# ps2.net
KiCad netlist of a schematic drawn in EAGLE
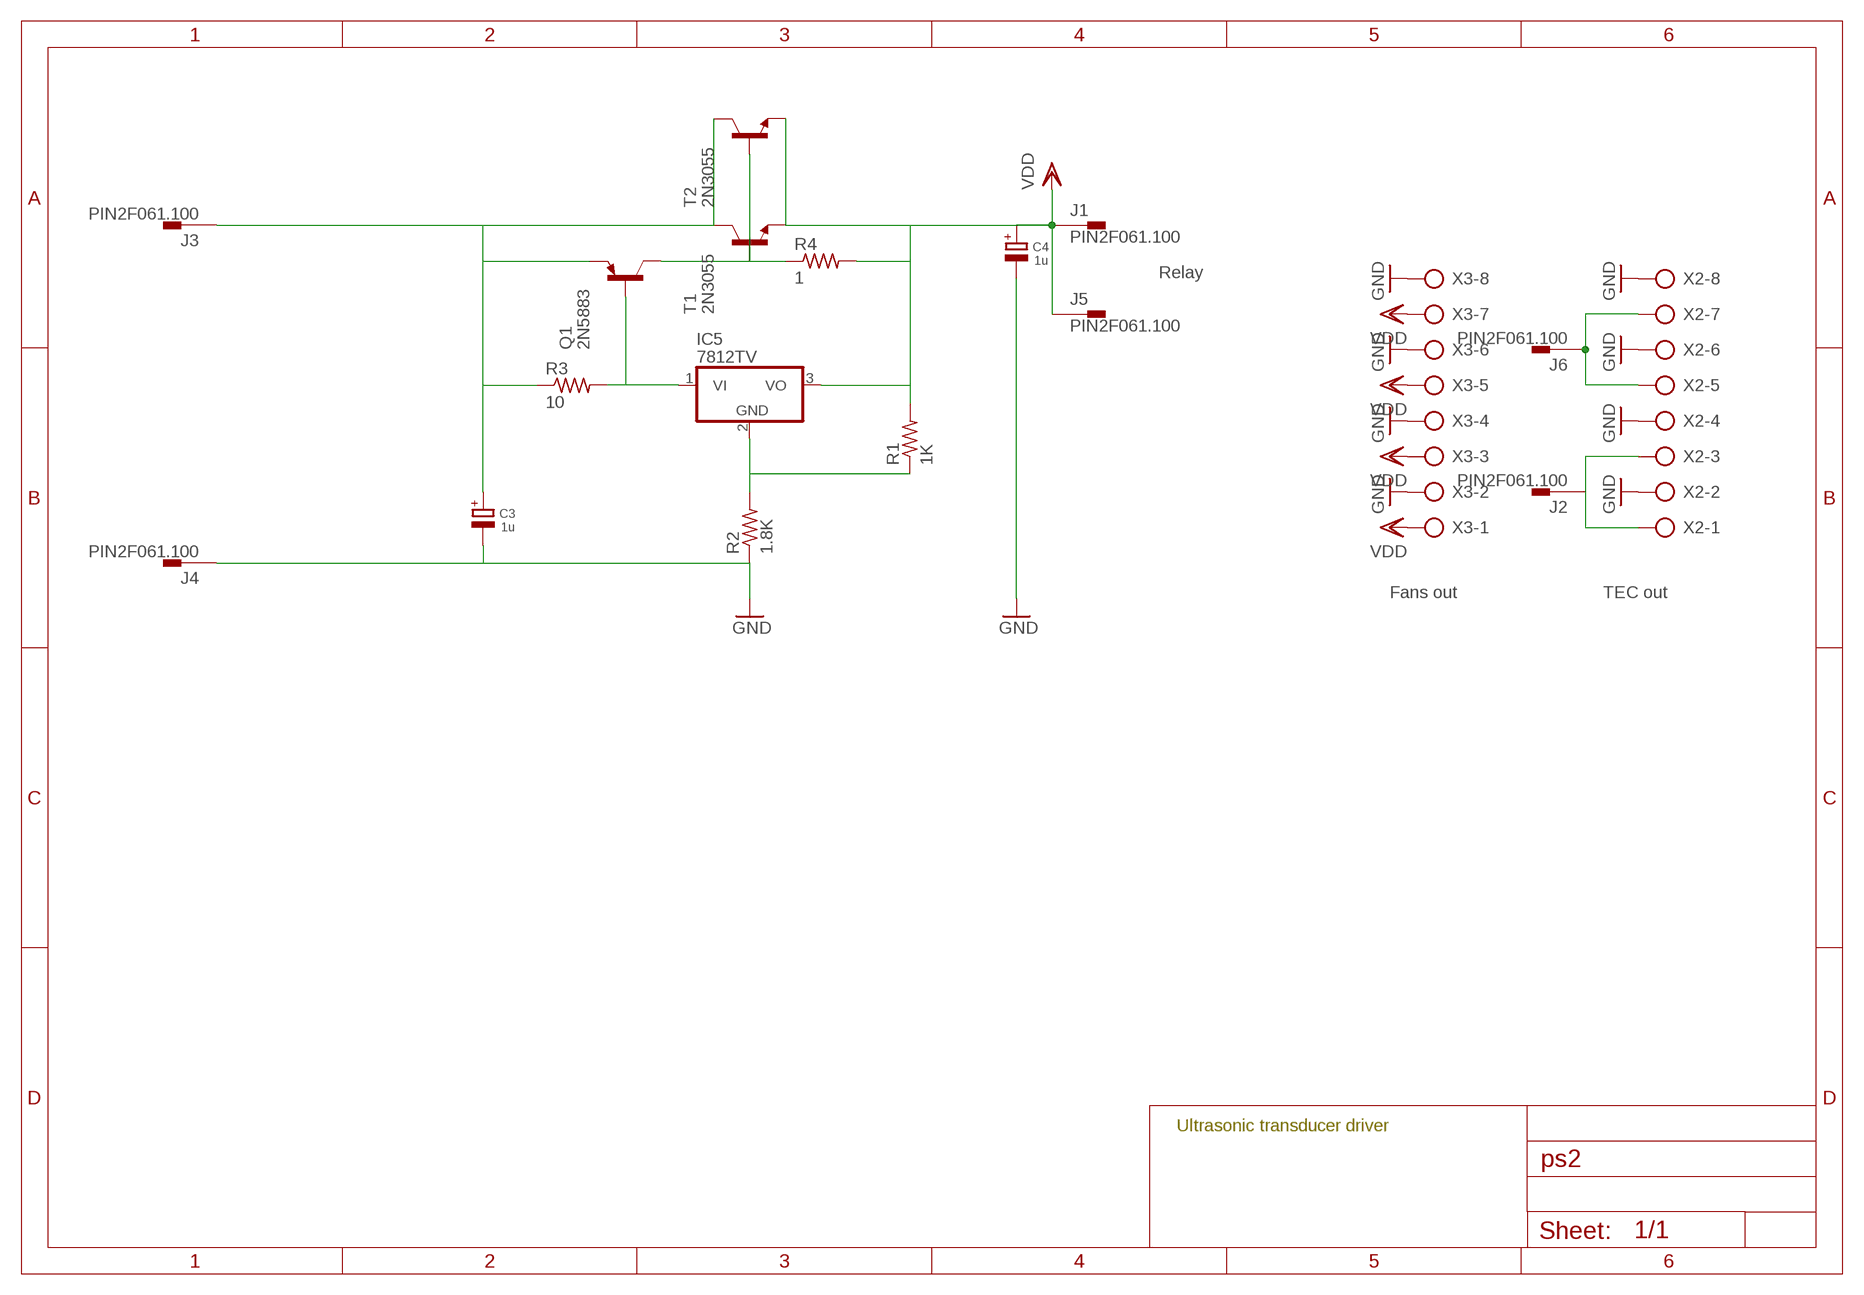
[diagram p0: schematic, sheet 1]

(export (version "E")
  (design (tool "Eeschema 10.0.6"))
  (components
    (comp (ref "C3")
      (value "1u")
      (footprint "eagle-import:EB20D")
      (libsource (lib "eagle-import") (part "CPOL-EUE10-20"))
    )
    (comp (ref "C4")
      (value "1u")
      (footprint "eagle-import:EB20D")
      (libsource (lib "eagle-import") (part "CPOL-EUE10-20"))
    )
    (comp (ref "IC5")
      (value "7812TV")
      (footprint "eagle-import:TO220V")
      (libsource (lib "eagle-import") (part "78TV12"))
    )
    (comp (ref "J1")
      (value "PIN2F061.100")
      (footprint "eagle-import:F061.100")
      (libsource (lib "eagle-import") (part "PIN2F061.100"))
    )
    (comp (ref "J2")
      (value "PIN2F061.100")
      (footprint "eagle-import:F061.100")
      (libsource (lib "eagle-import") (part "PIN2F061.100"))
    )
    (comp (ref "J3")
      (value "PIN2F061.100")
      (footprint "eagle-import:F061.100")
      (libsource (lib "eagle-import") (part "PIN2F061.100"))
    )
    (comp (ref "J4")
      (value "PIN2F061.100")
      (footprint "eagle-import:F061.100")
      (libsource (lib "eagle-import") (part "PIN2F061.100"))
    )
    (comp (ref "J5")
      (value "PIN2F061.100")
      (footprint "eagle-import:F061.100")
      (libsource (lib "eagle-import") (part "PIN2F061.100"))
    )
    (comp (ref "J6")
      (value "PIN2F061.100")
      (footprint "eagle-import:F061.100")
      (libsource (lib "eagle-import") (part "PIN2F061.100"))
    )
    (comp (ref "Q1")
      (value "2N5883")
      (footprint "eagle-import:TO3")
      (libsource (lib "eagle-import") (part "2N4905"))
    )
    (comp (ref "R1")
      (value "1K")
      (footprint "eagle-import:0207_15")
      (libsource (lib "eagle-import") (part "R-US_0207/15"))
    )
    (comp (ref "R2")
      (value "1.8K")
      (footprint "eagle-import:0207_15")
      (libsource (lib "eagle-import") (part "R-US_0207/15"))
    )
    (comp (ref "R3")
      (value "10")
      (footprint "eagle-import:0207_15")
      (libsource (lib "eagle-import") (part "R-US_0207/15"))
    )
    (comp (ref "R4")
      (value "1")
      (footprint "eagle-import:0922_22")
      (libsource (lib "eagle-import") (part "R-US_0922/22"))
    )
    (comp (ref "T1")
      (value "2N3055")
      (footprint "eagle-import:TO3")
      (libsource (lib "eagle-import") (part "2N3055"))
    )
    (comp (ref "T2")
      (value "2N3055")
      (footprint "eagle-import:TO3")
      (libsource (lib "eagle-import") (part "2N3055"))
    )
    (comp (ref "X2")
      (value "AK300/8")
      (footprint "eagle-import:AK300_8")
      (libsource (lib "eagle-import") (part "AK300/8"))
    )
    (comp (ref "X3")
      (value "AK300/8")
      (footprint "eagle-import:AK300_8")
      (libsource (lib "eagle-import") (part "AK300/8"))
    )
  )
  (nets
    (net (code "1") (name "GND") (class "Default")
      (node (ref "C3") (pin "-") (pinfunction "-_-") (pintype "passive"))
      (node (ref "C4") (pin "-") (pinfunction "-_-") (pintype "passive"))
      (node (ref "J4") (pin "A1") (pinfunction "1_A1") (pintype "passive"))
      (node (ref "J4") (pin "A2") (pinfunction "1_A2") (pintype "passive"))
      (node (ref "R2") (pin "1") (pinfunction "1_1") (pintype "passive"))
      (node (ref "X2") (pin "2") (pinfunction "KL_2") (pintype "passive"))
      (node (ref "X2") (pin "4") (pinfunction "KL_4") (pintype "passive"))
      (node (ref "X2") (pin "6") (pinfunction "KL_6") (pintype "passive"))
      (node (ref "X2") (pin "8") (pinfunction "KL_8") (pintype "passive"))
      (node (ref "X3") (pin "2") (pinfunction "KL_2") (pintype "passive"))
      (node (ref "X3") (pin "4") (pinfunction "KL_4") (pintype "passive"))
      (node (ref "X3") (pin "6") (pinfunction "KL_6") (pintype "passive"))
      (node (ref "X3") (pin "8") (pinfunction "KL_8") (pintype "passive"))
    )
    (net (code "2") (name "Net-(C3-Pad+)") (class "Default")
      (node (ref "C3") (pin "+") (pinfunction "+_+") (pintype "passive"))
      (node (ref "J3") (pin "A1") (pinfunction "1_A1") (pintype "passive"))
      (node (ref "J3") (pin "A2") (pinfunction "1_A2") (pintype "passive"))
      (node (ref "Q1") (pin "E") (pinfunction "E_E") (pintype "passive"))
      (node (ref "R3") (pin "1") (pinfunction "1_1") (pintype "passive"))
      (node (ref "T1") (pin "C") (pinfunction "C_C") (pintype "passive"))
      (node (ref "T1") (pin "C/") (pinfunction "C_C/") (pintype "passive"))
      (node (ref "T2") (pin "C") (pinfunction "C_C") (pintype "passive"))
      (node (ref "T2") (pin "C/") (pinfunction "C_C/") (pintype "passive"))
    )
    (net (code "3") (name "Net-(IC5-GND)") (class "Default")
      (node (ref "IC5") (pin "2") (pinfunction "GND_2") (pintype "passive"))
      (node (ref "R1") (pin "1") (pinfunction "1_1") (pintype "passive"))
      (node (ref "R2") (pin "2") (pinfunction "2_2") (pintype "passive"))
    )
    (net (code "4") (name "Net-(IC5-VI)") (class "Default")
      (node (ref "IC5") (pin "1") (pinfunction "VI_1") (pintype "input"))
      (node (ref "Q1") (pin "B") (pinfunction "B_B") (pintype "passive"))
      (node (ref "R3") (pin "2") (pinfunction "2_2") (pintype "passive"))
    )
    (net (code "5") (name "Net-(Q1-C-PadC{slash})") (class "Default")
      (node (ref "Q1") (pin "C") (pinfunction "C_C") (pintype "passive"))
      (node (ref "Q1") (pin "C/") (pinfunction "C_C/") (pintype "passive"))
      (node (ref "R4") (pin "1") (pinfunction "1_1") (pintype "passive"))
      (node (ref "T1") (pin "B") (pinfunction "B_B") (pintype "passive"))
      (node (ref "T2") (pin "B") (pinfunction "B_B") (pintype "passive"))
    )
    (net (code "6") (name "Net-(X2A-KL)") (class "Default")
      (node (ref "J2") (pin "A1") (pinfunction "1_A1") (pintype "passive"))
      (node (ref "J2") (pin "A2") (pinfunction "1_A2") (pintype "passive"))
      (node (ref "X2") (pin "1") (pinfunction "KL_1") (pintype "passive"))
      (node (ref "X2") (pin "3") (pinfunction "KL_3") (pintype "passive"))
    )
    (net (code "7") (name "Net-(X2E-KL)") (class "Default")
      (node (ref "J6") (pin "A1") (pinfunction "1_A1") (pintype "passive"))
      (node (ref "J6") (pin "A2") (pinfunction "1_A2") (pintype "passive"))
      (node (ref "X2") (pin "5") (pinfunction "KL_5") (pintype "passive"))
      (node (ref "X2") (pin "7") (pinfunction "KL_7") (pintype "passive"))
    )
    (net (code "8") (name "VDD") (class "Default")
      (node (ref "C4") (pin "+") (pinfunction "+_+") (pintype "passive"))
      (node (ref "IC5") (pin "3") (pinfunction "VO_3") (pintype "passive"))
      (node (ref "J1") (pin "A1") (pinfunction "1_A1") (pintype "passive"))
      (node (ref "J1") (pin "A2") (pinfunction "1_A2") (pintype "passive"))
      (node (ref "J5") (pin "A1") (pinfunction "1_A1") (pintype "passive"))
      (node (ref "J5") (pin "A2") (pinfunction "1_A2") (pintype "passive"))
      (node (ref "R1") (pin "2") (pinfunction "2_2") (pintype "passive"))
      (node (ref "R4") (pin "2") (pinfunction "2_2") (pintype "passive"))
      (node (ref "T1") (pin "E") (pinfunction "E_E") (pintype "passive"))
      (node (ref "T2") (pin "E") (pinfunction "E_E") (pintype "passive"))
      (node (ref "X3") (pin "1") (pinfunction "KL_1") (pintype "passive"))
      (node (ref "X3") (pin "3") (pinfunction "KL_3") (pintype "passive"))
      (node (ref "X3") (pin "5") (pinfunction "KL_5") (pintype "passive"))
      (node (ref "X3") (pin "7") (pinfunction "KL_7") (pintype "passive"))
    )
  )
)
